# control_board_v2.net
KiCad netlist of a schematic drawn in EAGLE
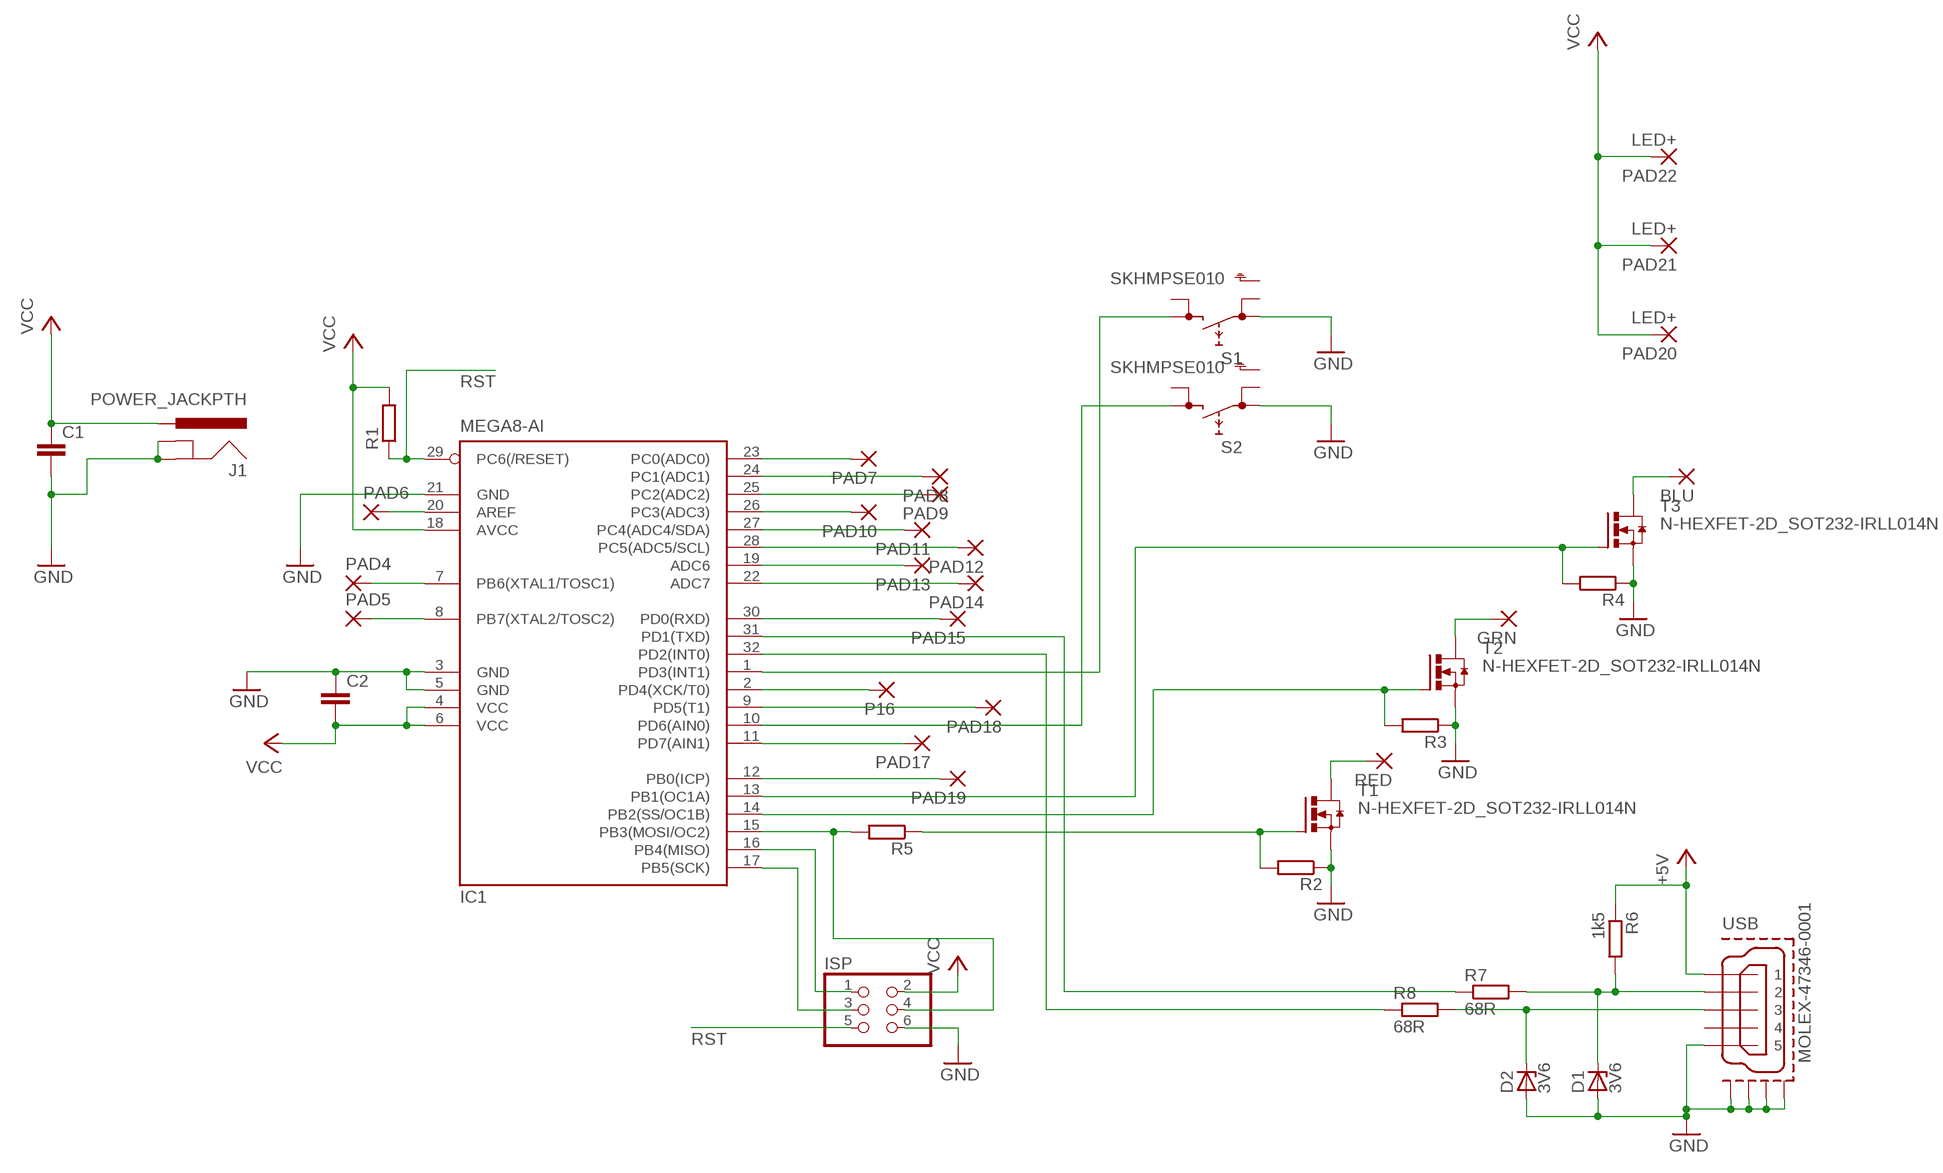
[diagram p0: schematic, sheet 1]

(export (version "E")
  (design (tool "Eeschema 10.0.6"))
  (components
    (comp (ref "BLU")
      (value "2,54/1,0")
      (footprint "eagle-import:2,54_1,0")
      (libsource (lib "eagle-import") (part "2,54/1,0"))
    )
    (comp (ref "C1")
      (value "C-EUC0805")
      (footprint "eagle-import:C0805")
      (libsource (lib "eagle-import") (part "C-EUC0805"))
    )
    (comp (ref "C2")
      (value "C-EUC0805")
      (footprint "eagle-import:C0805")
      (libsource (lib "eagle-import") (part "C-EUC0805"))
    )
    (comp (ref "D1")
      (value "3V6")
      (footprint "eagle-import:SOD80C")
      (libsource (lib "eagle-import") (part "ZENER-DIODESOD80C"))
    )
    (comp (ref "D2")
      (value "3V6")
      (footprint "eagle-import:SOD80C")
      (libsource (lib "eagle-import") (part "ZENER-DIODESOD80C"))
    )
    (comp (ref "GRN")
      (value "2,54/1,0")
      (footprint "eagle-import:2,54_1,0")
      (libsource (lib "eagle-import") (part "2,54/1,0"))
    )
    (comp (ref "IC1")
      (value "MEGA8-AI")
      (footprint "eagle-import:TQFP32-08")
      (fields (field (name "MPN") "ATMEGA8-16AU"))
      (libsource (lib "eagle-import") (part "MEGA8-AI"))
    )
    (comp (ref "ISP")
      (value "PINHD-2X3")
      (footprint "eagle-import:2X03")
      (libsource (lib "eagle-import") (part "PINHD-2X3"))
    )
    (comp (ref "J1")
      (value "POWER_JACKPTH")
      (footprint "eagle-import:POWER_JACK_PTH")
      (libsource (lib "eagle-import") (part "POWER_JACKPTH"))
    )
    (comp (ref "P16")
      (value "1,6/0,9")
      (footprint "eagle-import:1,6_0,9")
      (libsource (lib "eagle-import") (part "1,6/0,9"))
    )
    (comp (ref "PAD4")
      (value "1,6/0,9")
      (footprint "eagle-import:1,6_0,9")
      (libsource (lib "eagle-import") (part "1,6/0,9"))
    )
    (comp (ref "PAD5")
      (value "1,6/0,9")
      (footprint "eagle-import:1,6_0,9")
      (libsource (lib "eagle-import") (part "1,6/0,9"))
    )
    (comp (ref "PAD6")
      (value "1,6/0,9")
      (footprint "eagle-import:1,6_0,9")
      (libsource (lib "eagle-import") (part "1,6/0,9"))
    )
    (comp (ref "PAD7")
      (value "1,6/0,9")
      (footprint "eagle-import:1,6_0,9")
      (libsource (lib "eagle-import") (part "1,6/0,9"))
    )
    (comp (ref "PAD8")
      (value "1,6/0,9")
      (footprint "eagle-import:1,6_0,9")
      (libsource (lib "eagle-import") (part "1,6/0,9"))
    )
    (comp (ref "PAD9")
      (value "1,6/0,9")
      (footprint "eagle-import:1,6_0,9")
      (libsource (lib "eagle-import") (part "1,6/0,9"))
    )
    (comp (ref "PAD10")
      (value "1,6/0,9")
      (footprint "eagle-import:1,6_0,9")
      (libsource (lib "eagle-import") (part "1,6/0,9"))
    )
    (comp (ref "PAD11")
      (value "1,6/0,9")
      (footprint "eagle-import:1,6_0,9")
      (libsource (lib "eagle-import") (part "1,6/0,9"))
    )
    (comp (ref "PAD12")
      (value "1,6/0,9")
      (footprint "eagle-import:1,6_0,9")
      (libsource (lib "eagle-import") (part "1,6/0,9"))
    )
    (comp (ref "PAD13")
      (value "1,6/0,9")
      (footprint "eagle-import:1,6_0,9")
      (libsource (lib "eagle-import") (part "1,6/0,9"))
    )
    (comp (ref "PAD14")
      (value "1,6/0,9")
      (footprint "eagle-import:1,6_0,9")
      (libsource (lib "eagle-import") (part "1,6/0,9"))
    )
    (comp (ref "PAD15")
      (value "1,6/0,9")
      (footprint "eagle-import:1,6_0,9")
      (libsource (lib "eagle-import") (part "1,6/0,9"))
    )
    (comp (ref "PAD17")
      (value "1,6/0,9")
      (footprint "eagle-import:1,6_0,9")
      (libsource (lib "eagle-import") (part "1,6/0,9"))
    )
    (comp (ref "PAD18")
      (value "1,6/0,9")
      (footprint "eagle-import:1,6_0,9")
      (libsource (lib "eagle-import") (part "1,6/0,9"))
    )
    (comp (ref "PAD19")
      (value "1,6/0,9")
      (footprint "eagle-import:1,6_0,9")
      (libsource (lib "eagle-import") (part "1,6/0,9"))
    )
    (comp (ref "PAD20")
      (value "LED+")
      (footprint "eagle-import:2,54_1,0")
      (libsource (lib "eagle-import") (part "2,54/1,0"))
    )
    (comp (ref "PAD21")
      (value "LED+")
      (footprint "eagle-import:2,54_1,0")
      (libsource (lib "eagle-import") (part "2,54/1,0"))
    )
    (comp (ref "PAD22")
      (value "LED+")
      (footprint "eagle-import:2,54_1,0")
      (libsource (lib "eagle-import") (part "2,54/1,0"))
    )
    (comp (ref "R1")
      (value "R-EU_R0805")
      (footprint "eagle-import:R0805")
      (libsource (lib "eagle-import") (part "R-EU_R0805"))
    )
    (comp (ref "R2")
      (value "R-EU_R0805")
      (footprint "eagle-import:R0805")
      (libsource (lib "eagle-import") (part "R-EU_R0805"))
    )
    (comp (ref "R3")
      (value "R-EU_R0805")
      (footprint "eagle-import:R0805")
      (libsource (lib "eagle-import") (part "R-EU_R0805"))
    )
    (comp (ref "R4")
      (value "R-EU_R0805")
      (footprint "eagle-import:R0805")
      (libsource (lib "eagle-import") (part "R-EU_R0805"))
    )
    (comp (ref "R5")
      (value "R-EU_R0805")
      (footprint "eagle-import:R0805")
      (libsource (lib "eagle-import") (part "R-EU_R0805"))
    )
    (comp (ref "R6")
      (value "1k5")
      (footprint "eagle-import:R0805")
      (libsource (lib "eagle-import") (part "R-EU_R0805"))
    )
    (comp (ref "R7")
      (value "68R")
      (footprint "eagle-import:R0805")
      (libsource (lib "eagle-import") (part "R-EU_R0805"))
    )
    (comp (ref "R8")
      (value "68R")
      (footprint "eagle-import:R0805")
      (libsource (lib "eagle-import") (part "R-EU_R0805"))
    )
    (comp (ref "RED")
      (value "2,54/1,0")
      (footprint "eagle-import:2,54_1,0")
      (libsource (lib "eagle-import") (part "2,54/1,0"))
    )
    (comp (ref "S1")
      (value "SKHMPSE010")
      (footprint "eagle-import:SKHMPXE010")
      (libsource (lib "eagle-import") (part "SKHMPE010S"))
    )
    (comp (ref "S2")
      (value "SKHMPSE010")
      (footprint "eagle-import:SKHMPXE010")
      (libsource (lib "eagle-import") (part "SKHMPE010S"))
    )
    (comp (ref "T1")
      (value "N-HEXFET-2D_SOT232-IRLL014N")
      (footprint "eagle-import:SOT223")
      (libsource (lib "eagle-import") (part "N-HEXFET-2D_?-SOT232IRLL014N"))
    )
    (comp (ref "T2")
      (value "N-HEXFET-2D_SOT232-IRLL014N")
      (footprint "eagle-import:SOT223")
      (libsource (lib "eagle-import") (part "N-HEXFET-2D_?-SOT232IRLL014N"))
    )
    (comp (ref "T3")
      (value "N-HEXFET-2D_SOT232-IRLL014N")
      (footprint "eagle-import:SOT223")
      (libsource (lib "eagle-import") (part "N-HEXFET-2D_?-SOT232IRLL014N"))
    )
    (comp (ref "USB")
      (value "MOLEX-47346-0001")
      (footprint "eagle-import:MOLEX-47364-0001")
      (libsource (lib "eagle-import") (part "MOLEX-47346-0001"))
    )
  )
  (nets
    (net (code "1") (name "+5V") (class "Default")
      (node (ref "R6") (pin "1") (pinfunction "1_1") (pintype "passive"))
      (node (ref "USB") (pin "1") (pinfunction "1_1") (pintype "input"))
    )
    (net (code "2") (name "/RST") (class "Default")
      (node (ref "IC1") (pin "29") (pinfunction "PC6(/RESET)_29") (pintype "bidirectional"))
      (node (ref "ISP") (pin "5") (pinfunction "5_5") (pintype "passive"))
      (node (ref "R1") (pin "1") (pinfunction "1_1") (pintype "passive"))
    )
    (net (code "3") (name "GND") (class "Default")
      (node (ref "C1") (pin "2") (pinfunction "2_2") (pintype "passive"))
      (node (ref "C2") (pin "1") (pinfunction "1_1") (pintype "passive"))
      (node (ref "D1") (pin "A") (pinfunction "A_A") (pintype "passive"))
      (node (ref "D2") (pin "A") (pinfunction "A_A") (pintype "passive"))
      (node (ref "IC1") (pin "21") (pinfunction "GND_21") (pintype "power_in"))
      (node (ref "IC1") (pin "3") (pinfunction "GND_3") (pintype "power_in"))
      (node (ref "IC1") (pin "5") (pinfunction "GND_5") (pintype "power_in"))
      (node (ref "ISP") (pin "6") (pinfunction "6_6") (pintype "passive"))
      (node (ref "J1") (pin "GND") (pinfunction "GND_GND") (pintype "bidirectional"))
      (node (ref "J1") (pin "GNDBREAK") (pinfunction "GNDBREAK_GNDBREAK") (pintype "bidirectional"))
      (node (ref "R2") (pin "1") (pinfunction "1_1") (pintype "passive"))
      (node (ref "R3") (pin "1") (pinfunction "1_1") (pintype "passive"))
      (node (ref "R4") (pin "1") (pinfunction "1_1") (pintype "passive"))
      (node (ref "S1") (pin "1") (pinfunction "1.1_1") (pintype "passive"))
      (node (ref "S2") (pin "1") (pinfunction "1.1_1") (pintype "passive"))
      (node (ref "T1") (pin "3") (pinfunction "S_3") (pintype "passive"))
      (node (ref "T2") (pin "3") (pinfunction "S_3") (pintype "passive"))
      (node (ref "T3") (pin "3") (pinfunction "S_3") (pintype "passive"))
      (node (ref "USB") (pin "5") (pinfunction "5_5") (pintype "input"))
      (node (ref "USB") (pin "GND1") (pinfunction "GND1_GND1") (pintype "bidirectional"))
      (node (ref "USB") (pin "GND2") (pinfunction "GND2_GND2") (pintype "bidirectional"))
      (node (ref "USB") (pin "GND3") (pinfunction "GND3_GND3") (pintype "bidirectional"))
      (node (ref "USB") (pin "GND4") (pinfunction "GND4_GND4") (pintype "bidirectional"))
    )
    (net (code "4") (name "Net-(BLU-P)") (class "Default")
      (node (ref "BLU") (pin "1") (pinfunction "P_1") (pintype "passive"))
      (node (ref "T3") (pin "2") (pinfunction "D_2") (pintype "passive"))
      (node (ref "T3") (pin "4") (pinfunction "D_4") (pintype "passive"))
    )
    (net (code "5") (name "Net-(D1-PadC)") (class "Default")
      (node (ref "D1") (pin "C") (pinfunction "C_C") (pintype "passive"))
      (node (ref "R6") (pin "2") (pinfunction "2_2") (pintype "passive"))
      (node (ref "R7") (pin "2") (pinfunction "2_2") (pintype "passive"))
      (node (ref "USB") (pin "2") (pinfunction "2_2") (pintype "input"))
    )
    (net (code "6") (name "Net-(D2-PadC)") (class "Default")
      (node (ref "D2") (pin "C") (pinfunction "C_C") (pintype "passive"))
      (node (ref "R8") (pin "2") (pinfunction "2_2") (pintype "passive"))
      (node (ref "USB") (pin "3") (pinfunction "3_3") (pintype "input"))
    )
    (net (code "7") (name "Net-(GRN-P)") (class "Default")
      (node (ref "GRN") (pin "1") (pinfunction "P_1") (pintype "passive"))
      (node (ref "T2") (pin "2") (pinfunction "D_2") (pintype "passive"))
      (node (ref "T2") (pin "4") (pinfunction "D_4") (pintype "passive"))
    )
    (net (code "8") (name "Net-(IC1-ADC6)") (class "Default")
      (node (ref "IC1") (pin "19") (pinfunction "ADC6_19") (pintype "bidirectional"))
      (node (ref "PAD13") (pin "1") (pinfunction "P_1") (pintype "passive"))
    )
    (net (code "9") (name "Net-(IC1-ADC7)") (class "Default")
      (node (ref "IC1") (pin "22") (pinfunction "ADC7_22") (pintype "bidirectional"))
      (node (ref "PAD14") (pin "1") (pinfunction "P_1") (pintype "passive"))
    )
    (net (code "10") (name "Net-(IC1-AREF)") (class "Default")
      (node (ref "IC1") (pin "20") (pinfunction "AREF_20") (pintype "passive"))
      (node (ref "PAD6") (pin "1") (pinfunction "P_1") (pintype "passive"))
    )
    (net (code "11") (name "Net-(IC1-PB0(ICP))") (class "Default")
      (node (ref "IC1") (pin "12") (pinfunction "PB0(ICP)_12") (pintype "bidirectional"))
      (node (ref "PAD19") (pin "1") (pinfunction "P_1") (pintype "passive"))
    )
    (net (code "12") (name "Net-(IC1-PB1(OC1A))") (class "Default")
      (node (ref "IC1") (pin "13") (pinfunction "PB1(OC1A)_13") (pintype "bidirectional"))
      (node (ref "R4") (pin "2") (pinfunction "2_2") (pintype "passive"))
      (node (ref "T3") (pin "1") (pinfunction "G_1") (pintype "passive"))
    )
    (net (code "13") (name "Net-(IC1-PB2(SS{slash}OC1B))") (class "Default")
      (node (ref "IC1") (pin "14") (pinfunction "PB2(SS/OC1B)_14") (pintype "bidirectional"))
      (node (ref "R3") (pin "2") (pinfunction "2_2") (pintype "passive"))
      (node (ref "T2") (pin "1") (pinfunction "G_1") (pintype "passive"))
    )
    (net (code "14") (name "Net-(IC1-PB3(MOSI{slash}OC2))") (class "Default")
      (node (ref "IC1") (pin "15") (pinfunction "PB3(MOSI/OC2)_15") (pintype "bidirectional"))
      (node (ref "ISP") (pin "4") (pinfunction "4_4") (pintype "passive"))
      (node (ref "R5") (pin "2") (pinfunction "2_2") (pintype "passive"))
    )
    (net (code "15") (name "Net-(IC1-PB4(MISO))") (class "Default")
      (node (ref "IC1") (pin "16") (pinfunction "PB4(MISO)_16") (pintype "bidirectional"))
      (node (ref "ISP") (pin "1") (pinfunction "1_1") (pintype "passive"))
    )
    (net (code "16") (name "Net-(IC1-PB5(SCK))") (class "Default")
      (node (ref "IC1") (pin "17") (pinfunction "PB5(SCK)_17") (pintype "bidirectional"))
      (node (ref "ISP") (pin "3") (pinfunction "3_3") (pintype "passive"))
    )
    (net (code "17") (name "Net-(IC1-PB6(XTAL1{slash}TOSC1))") (class "Default")
      (node (ref "IC1") (pin "7") (pinfunction "PB6(XTAL1/TOSC1)_7") (pintype "bidirectional"))
      (node (ref "PAD4") (pin "1") (pinfunction "P_1") (pintype "passive"))
    )
    (net (code "18") (name "Net-(IC1-PB7(XTAL2{slash}TOSC2))") (class "Default")
      (node (ref "IC1") (pin "8") (pinfunction "PB7(XTAL2/TOSC2)_8") (pintype "bidirectional"))
      (node (ref "PAD5") (pin "1") (pinfunction "P_1") (pintype "passive"))
    )
    (net (code "19") (name "Net-(IC1-PC0(ADC0))") (class "Default")
      (node (ref "IC1") (pin "23") (pinfunction "PC0(ADC0)_23") (pintype "bidirectional"))
      (node (ref "PAD7") (pin "1") (pinfunction "P_1") (pintype "passive"))
    )
    (net (code "20") (name "Net-(IC1-PC1(ADC1))") (class "Default")
      (node (ref "IC1") (pin "24") (pinfunction "PC1(ADC1)_24") (pintype "bidirectional"))
      (node (ref "PAD8") (pin "1") (pinfunction "P_1") (pintype "passive"))
    )
    (net (code "21") (name "Net-(IC1-PC2(ADC2))") (class "Default")
      (node (ref "IC1") (pin "25") (pinfunction "PC2(ADC2)_25") (pintype "bidirectional"))
      (node (ref "PAD9") (pin "1") (pinfunction "P_1") (pintype "passive"))
    )
    (net (code "22") (name "Net-(IC1-PC3(ADC3))") (class "Default")
      (node (ref "IC1") (pin "26") (pinfunction "PC3(ADC3)_26") (pintype "bidirectional"))
      (node (ref "PAD10") (pin "1") (pinfunction "P_1") (pintype "passive"))
    )
    (net (code "23") (name "Net-(IC1-PC4(ADC4{slash}SDA))") (class "Default")
      (node (ref "IC1") (pin "27") (pinfunction "PC4(ADC4/SDA)_27") (pintype "bidirectional"))
      (node (ref "PAD11") (pin "1") (pinfunction "P_1") (pintype "passive"))
    )
    (net (code "24") (name "Net-(IC1-PC5(ADC5{slash}SCL))") (class "Default")
      (node (ref "IC1") (pin "28") (pinfunction "PC5(ADC5/SCL)_28") (pintype "bidirectional"))
      (node (ref "PAD12") (pin "1") (pinfunction "P_1") (pintype "passive"))
    )
    (net (code "25") (name "Net-(IC1-PD0(RXD))") (class "Default")
      (node (ref "IC1") (pin "30") (pinfunction "PD0(RXD)_30") (pintype "bidirectional"))
      (node (ref "PAD15") (pin "1") (pinfunction "P_1") (pintype "passive"))
    )
    (net (code "26") (name "Net-(IC1-PD1(TXD))") (class "Default")
      (node (ref "IC1") (pin "31") (pinfunction "PD1(TXD)_31") (pintype "bidirectional"))
      (node (ref "R7") (pin "1") (pinfunction "1_1") (pintype "passive"))
    )
    (net (code "27") (name "Net-(IC1-PD2(INT0))") (class "Default")
      (node (ref "IC1") (pin "32") (pinfunction "PD2(INT0)_32") (pintype "bidirectional"))
      (node (ref "R8") (pin "1") (pinfunction "1_1") (pintype "passive"))
    )
    (net (code "28") (name "Net-(IC1-PD3(INT1))") (class "Default")
      (node (ref "IC1") (pin "1") (pinfunction "PD3(INT1)_1") (pintype "bidirectional"))
      (node (ref "S1") (pin "3") (pinfunction "2.1_3") (pintype "passive"))
    )
    (net (code "29") (name "Net-(IC1-PD4(XCK{slash}T0))") (class "Default")
      (node (ref "IC1") (pin "2") (pinfunction "PD4(XCK/T0)_2") (pintype "bidirectional"))
      (node (ref "P16") (pin "1") (pinfunction "P_1") (pintype "passive"))
    )
    (net (code "30") (name "Net-(IC1-PD5(T1))") (class "Default")
      (node (ref "IC1") (pin "9") (pinfunction "PD5(T1)_9") (pintype "bidirectional"))
      (node (ref "PAD18") (pin "1") (pinfunction "P_1") (pintype "passive"))
    )
    (net (code "31") (name "Net-(IC1-PD6(AIN0))") (class "Default")
      (node (ref "IC1") (pin "10") (pinfunction "PD6(AIN0)_10") (pintype "bidirectional"))
      (node (ref "S2") (pin "3") (pinfunction "2.1_3") (pintype "passive"))
    )
    (net (code "32") (name "Net-(IC1-PD7(AIN1))") (class "Default")
      (node (ref "IC1") (pin "11") (pinfunction "PD7(AIN1)_11") (pintype "bidirectional"))
      (node (ref "PAD17") (pin "1") (pinfunction "P_1") (pintype "passive"))
    )
    (net (code "33") (name "Net-(RED-P)") (class "Default")
      (node (ref "RED") (pin "1") (pinfunction "P_1") (pintype "passive"))
      (node (ref "T1") (pin "2") (pinfunction "D_2") (pintype "passive"))
      (node (ref "T1") (pin "4") (pinfunction "D_4") (pintype "passive"))
    )
    (net (code "34") (name "Net-(T1-G)") (class "Default")
      (node (ref "R2") (pin "2") (pinfunction "2_2") (pintype "passive"))
      (node (ref "R5") (pin "1") (pinfunction "1_1") (pintype "passive"))
      (node (ref "T1") (pin "1") (pinfunction "G_1") (pintype "passive"))
    )
    (net (code "35") (name "VCC") (class "Default")
      (node (ref "C1") (pin "1") (pinfunction "1_1") (pintype "passive"))
      (node (ref "C2") (pin "2") (pinfunction "2_2") (pintype "passive"))
      (node (ref "IC1") (pin "18") (pinfunction "AVCC_18") (pintype "power_in"))
      (node (ref "IC1") (pin "4") (pinfunction "VCC_4") (pintype "power_in"))
      (node (ref "IC1") (pin "6") (pinfunction "VCC_6") (pintype "power_in"))
      (node (ref "ISP") (pin "2") (pinfunction "2_2") (pintype "passive"))
      (node (ref "J1") (pin "PWR") (pinfunction "PWR_PWR") (pintype "bidirectional"))
      (node (ref "PAD20") (pin "1") (pinfunction "P_1") (pintype "passive"))
      (node (ref "PAD21") (pin "1") (pinfunction "P_1") (pintype "passive"))
      (node (ref "PAD22") (pin "1") (pinfunction "P_1") (pintype "passive"))
      (node (ref "R1") (pin "2") (pinfunction "2_2") (pintype "passive"))
    )
    (net (code "36") (name "unconnected-(S1-1.2-Pad2)") (class "Default")
      (node (ref "S1") (pin "2") (pinfunction "1.2_2") (pintype "passive"))
    )
    (net (code "37") (name "unconnected-(S1-2.2-Pad4)") (class "Default")
      (node (ref "S1") (pin "4") (pinfunction "2.2_4") (pintype "passive"))
    )
    (net (code "38") (name "unconnected-(S1-SH-Pad5)") (class "Default")
      (node (ref "S1") (pin "5") (pinfunction "SH_5") (pintype "passive"))
    )
    (net (code "39") (name "unconnected-(S2-1.2-Pad2)") (class "Default")
      (node (ref "S2") (pin "2") (pinfunction "1.2_2") (pintype "passive"))
    )
    (net (code "40") (name "unconnected-(S2-2.2-Pad4)") (class "Default")
      (node (ref "S2") (pin "4") (pinfunction "2.2_4") (pintype "passive"))
    )
    (net (code "41") (name "unconnected-(S2-SH-Pad5)") (class "Default")
      (node (ref "S2") (pin "5") (pinfunction "SH_5") (pintype "passive"))
    )
    (net (code "42") (name "unconnected-(USB-Pad4)") (class "Default")
      (node (ref "USB") (pin "4") (pinfunction "4_4") (pintype "input"))
    )
  )
)
